# SMD_optek_driver_led-mosfet002.net
KiCad netlist of a schematic drawn in EAGLE
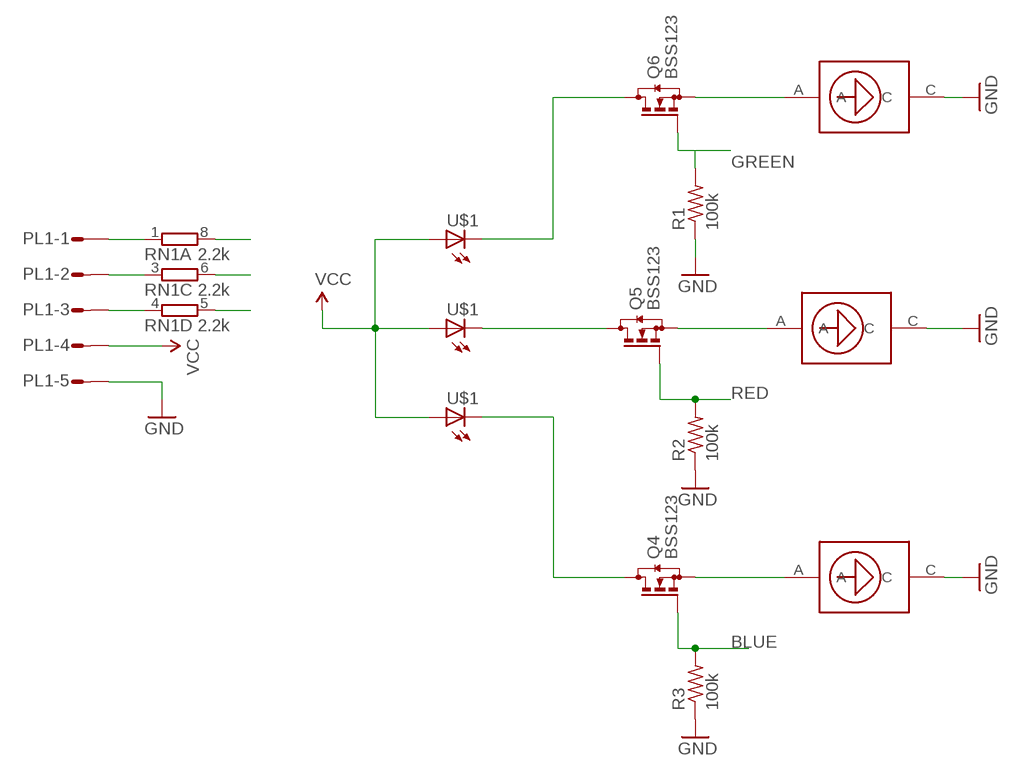
[diagram p0: schematic, sheet 1]

(export (version "E")
  (design (tool "Eeschema 10.0.6"))
  (components
    (comp (ref "PL1")
      (value "DF3-05R")
      (footprint "eagle-import:DF3R-05")
      (libsource (lib "eagle-import") (part "DF3-05R"))
    )
    (comp (ref "Q4")
      (value "BSS123")
      (footprint "eagle-import:SOT23")
      (libsource (lib "eagle-import") (part "BSS123"))
    )
    (comp (ref "Q5")
      (value "BSS123")
      (footprint "eagle-import:SOT23")
      (libsource (lib "eagle-import") (part "BSS123"))
    )
    (comp (ref "Q6")
      (value "BSS123")
      (footprint "eagle-import:SOT23")
      (libsource (lib "eagle-import") (part "BSS123"))
    )
    (comp (ref "R1")
      (value "100k")
      (footprint "eagle-import:R0402")
      (libsource (lib "eagle-import") (part "R-US_R0402"))
    )
    (comp (ref "R2")
      (value "100k")
      (footprint "eagle-import:R0402")
      (libsource (lib "eagle-import") (part "R-US_R0402"))
    )
    (comp (ref "R3")
      (value "100k")
      (footprint "eagle-import:R0402")
      (libsource (lib "eagle-import") (part "R-US_R0402"))
    )
    (comp (ref "RN1")
      (value "2.2k")
      (footprint "eagle-import:0603-ARC")
      (libsource (lib "eagle-import") (part "4R-N0603-ARC"))
    )
    (comp (ref "U$1")
      (value "OVSPRGBCR4")
      (footprint "eagle-import:OVSPRGBCR4")
      (libsource (lib "eagle-import") (part "OVSPRGBCR4"))
    )
    (comp (ref "U$2")
      (value "NSI50350AST3G")
      (footprint "eagle-import:SMC-2")
      (libsource (lib "eagle-import") (part "NSI50350AST3G"))
    )
    (comp (ref "U$3")
      (value "NSI50350AST3G")
      (footprint "eagle-import:SMC-2")
      (libsource (lib "eagle-import") (part "NSI50350AST3G"))
    )
    (comp (ref "U$4")
      (value "NSI50350AST3G")
      (footprint "eagle-import:SMC-2")
      (libsource (lib "eagle-import") (part "NSI50350AST3G"))
    )
  )
  (nets
    (net (code "1") (name "/BLUE") (class "Default")
      (node (ref "Q4") (pin "1") (pinfunction "G_1") (pintype "passive"))
      (node (ref "R3") (pin "2") (pinfunction "2_2") (pintype "passive"))
      (node (ref "RN1") (pin "5") (pinfunction "2_5") (pintype "passive"))
    )
    (net (code "2") (name "/GREEN") (class "Default")
      (node (ref "Q6") (pin "1") (pinfunction "G_1") (pintype "passive"))
      (node (ref "R1") (pin "2") (pinfunction "2_2") (pintype "passive"))
      (node (ref "RN1") (pin "8") (pinfunction "2_8") (pintype "passive"))
    )
    (net (code "3") (name "/RED") (class "Default")
      (node (ref "Q5") (pin "1") (pinfunction "G_1") (pintype "passive"))
      (node (ref "R2") (pin "2") (pinfunction "2_2") (pintype "passive"))
      (node (ref "RN1") (pin "6") (pinfunction "2_6") (pintype "passive"))
    )
    (net (code "4") (name "GND") (class "Default")
      (node (ref "PL1") (pin "5") (pinfunction "S_5") (pintype "passive"))
      (node (ref "R1") (pin "1") (pinfunction "1_1") (pintype "passive"))
      (node (ref "R2") (pin "1") (pinfunction "1_1") (pintype "passive"))
      (node (ref "R3") (pin "1") (pinfunction "1_1") (pintype "passive"))
      (node (ref "U$2") (pin "C") (pinfunction "C_C") (pintype "bidirectional"))
      (node (ref "U$3") (pin "C") (pinfunction "C_C") (pintype "bidirectional"))
      (node (ref "U$4") (pin "C") (pinfunction "C_C") (pintype "bidirectional"))
    )
    (net (code "5") (name "Net-(PL1A-S)") (class "Default")
      (node (ref "PL1") (pin "1") (pinfunction "S_1") (pintype "passive"))
      (node (ref "RN1") (pin "1") (pinfunction "1_1") (pintype "passive"))
    )
    (net (code "6") (name "Net-(PL1B-S)") (class "Default")
      (node (ref "PL1") (pin "2") (pinfunction "S_2") (pintype "passive"))
      (node (ref "RN1") (pin "3") (pinfunction "1_3") (pintype "passive"))
    )
    (net (code "7") (name "Net-(PL1C-S)") (class "Default")
      (node (ref "PL1") (pin "3") (pinfunction "S_3") (pintype "passive"))
      (node (ref "RN1") (pin "4") (pinfunction "1_4") (pintype "passive"))
    )
    (net (code "8") (name "Net-(Q4-D)") (class "Default")
      (node (ref "Q4") (pin "3") (pinfunction "D_3") (pintype "passive"))
      (node (ref "U$1") (pin "4") (pinfunction "BLUE_C_4") (pintype "passive"))
    )
    (net (code "9") (name "Net-(Q4-S)") (class "Default")
      (node (ref "Q4") (pin "2") (pinfunction "S_2") (pintype "passive"))
      (node (ref "U$4") (pin "A") (pinfunction "A_A") (pintype "bidirectional"))
    )
    (net (code "10") (name "Net-(Q5-D)") (class "Default")
      (node (ref "Q5") (pin "3") (pinfunction "D_3") (pintype "passive"))
      (node (ref "U$1") (pin "5") (pinfunction "RED_C_5") (pintype "passive"))
    )
    (net (code "11") (name "Net-(Q5-S)") (class "Default")
      (node (ref "Q5") (pin "2") (pinfunction "S_2") (pintype "passive"))
      (node (ref "U$3") (pin "A") (pinfunction "A_A") (pintype "bidirectional"))
    )
    (net (code "12") (name "Net-(Q6-D)") (class "Default")
      (node (ref "Q6") (pin "3") (pinfunction "D_3") (pintype "passive"))
      (node (ref "U$1") (pin "6") (pinfunction "GREEN_C_6") (pintype "passive"))
    )
    (net (code "13") (name "Net-(Q6-S)") (class "Default")
      (node (ref "Q6") (pin "2") (pinfunction "S_2") (pintype "passive"))
      (node (ref "U$2") (pin "A") (pinfunction "A_A") (pintype "bidirectional"))
    )
    (net (code "14") (name "VCC") (class "Default")
      (node (ref "PL1") (pin "4") (pinfunction "S_4") (pintype "passive"))
      (node (ref "U$1") (pin "1") (pinfunction "GREEN_A_1") (pintype "passive"))
      (node (ref "U$1") (pin "2") (pinfunction "RED_A_2") (pintype "passive"))
      (node (ref "U$1") (pin "3") (pinfunction "BLUE_A_3") (pintype "passive"))
    )
  )
)
